# NCS_Wireless_Control_Card_Display_Connec.net
KiCad netlist of a schematic drawn in Altium Designer
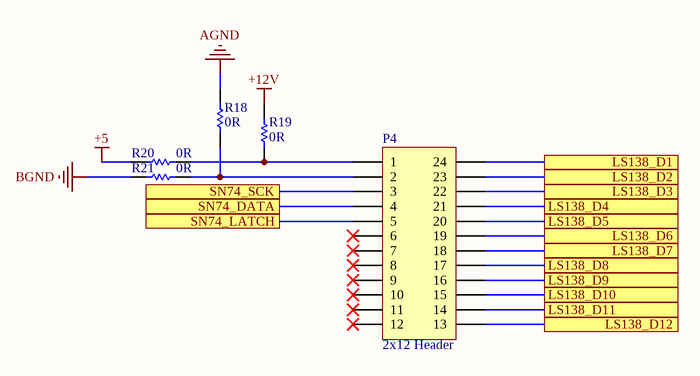
[diagram p0: NCS_Wireless_Control_Card_Display_Connector.SchDoc]

(export (version "E")
  (design (tool "Eeschema 10.0.6"))
  (components
    (comp (ref "P4")
      (value "2x12 Header")
      (footprint "2x12 header")
      (description "2.54mm Pitch C-Grid Header Low Profile Dual Row Vertical Shrouded 24 Circuits 0.38")
      (fields (field (name "MANUFACTURER") "Molex") (field (name "MANUFACTURER PART NUMBER") "0702462401"))
      (libsource (lib "schlib") (part "0702462401"))
    )
    (comp (ref "R18")
      (value "0R")
      (footprint "RC0805FR-7W330RL")
      (description "Res Thick Film 0805 330 Ohm 1% 0.25W(1/4W) ±200ppm/C Pad SMD T/R")
      (fields
        (field (name "MANUFACTURER") "Yageo")
        (field (name "MANUFACTURER PART NUMBER") "RC0805FR-7W330RL")
      )
      (libsource (lib "schlib") (part "RC0805FR-7W330RL"))
    )
    (comp (ref "R19")
      (value "0R")
      (footprint "RC0805FR-7W330RL")
      (description "Res Thick Film 0805 330 Ohm 1% 0.25W(1/4W) ±200ppm/C Pad SMD T/R")
      (fields
        (field (name "MANUFACTURER") "Yageo")
        (field (name "MANUFACTURER PART NUMBER") "RC0805FR-7W330RL")
      )
      (libsource (lib "schlib") (part "RC0805FR-7W330RL"))
    )
    (comp (ref "R20")
      (value "0R")
      (footprint "RC0805FR-7W330RL")
      (description "Res Thick Film 0805 330 Ohm 1% 0.25W(1/4W) ±200ppm/C Pad SMD T/R")
      (fields
        (field (name "MANUFACTURER") "Yageo")
        (field (name "MANUFACTURER PART NUMBER") "RC0805FR-7W330RL")
      )
      (libsource (lib "schlib") (part "RC0805FR-7W330RL"))
    )
    (comp (ref "R21")
      (value "0R")
      (footprint "RC0805FR-7W330RL")
      (description "Res Thick Film 0805 330 Ohm 1% 0.25W(1/4W) ±200ppm/C Pad SMD T/R")
      (fields
        (field (name "MANUFACTURER") "Yageo")
        (field (name "MANUFACTURER PART NUMBER") "RC0805FR-7W330RL")
      )
      (libsource (lib "schlib") (part "RC0805FR-7W330RL"))
    )
  )
  (nets
    (net (code "1") (name "+5") (class "Default")
      (node (ref "R20") (pin "2") (pinfunction "2_2") (pintype "passive"))
    )
    (net (code "2") (name "+12V") (class "Default")
      (node (ref "R19") (pin "2") (pinfunction "2_2") (pintype "passive"))
    )
    (net (code "3") (name "/LS138_D1") (class "Default")
      (node (ref "P4") (pin "24") (pinfunction "24_24") (pintype "passive"))
    )
    (net (code "4") (name "/LS138_D2") (class "Default")
      (node (ref "P4") (pin "23") (pinfunction "23_23") (pintype "passive"))
    )
    (net (code "5") (name "/LS138_D3") (class "Default")
      (node (ref "P4") (pin "22") (pinfunction "22_22") (pintype "passive"))
    )
    (net (code "6") (name "/LS138_D4") (class "Default")
      (node (ref "P4") (pin "21") (pinfunction "21_21") (pintype "passive"))
    )
    (net (code "7") (name "/LS138_D5") (class "Default")
      (node (ref "P4") (pin "20") (pinfunction "20_20") (pintype "passive"))
    )
    (net (code "8") (name "/LS138_D6") (class "Default")
      (node (ref "P4") (pin "19") (pinfunction "19_19") (pintype "passive"))
    )
    (net (code "9") (name "/LS138_D7") (class "Default")
      (node (ref "P4") (pin "18") (pinfunction "18_18") (pintype "passive"))
    )
    (net (code "10") (name "/LS138_D8") (class "Default")
      (node (ref "P4") (pin "17") (pinfunction "17_17") (pintype "passive"))
    )
    (net (code "11") (name "/LS138_D9") (class "Default")
      (node (ref "P4") (pin "16") (pinfunction "16_16") (pintype "passive"))
    )
    (net (code "12") (name "/LS138_D10") (class "Default")
      (node (ref "P4") (pin "15") (pinfunction "15_15") (pintype "passive"))
    )
    (net (code "13") (name "/LS138_D11") (class "Default")
      (node (ref "P4") (pin "14") (pinfunction "14_14") (pintype "passive"))
    )
    (net (code "14") (name "/LS138_D12") (class "Default")
      (node (ref "P4") (pin "13") (pinfunction "13_13") (pintype "passive"))
    )
    (net (code "15") (name "/SN74_DATA") (class "Default")
      (node (ref "P4") (pin "4") (pinfunction "4_4") (pintype "passive"))
    )
    (net (code "16") (name "/SN74_LATCH") (class "Default")
      (node (ref "P4") (pin "5") (pinfunction "5_5") (pintype "passive"))
    )
    (net (code "17") (name "/SN74_SCK") (class "Default")
      (node (ref "P4") (pin "3") (pinfunction "3_3") (pintype "passive"))
    )
    (net (code "18") (name "AGND") (class "Default")
      (node (ref "R18") (pin "2") (pinfunction "2_2") (pintype "passive"))
    )
    (net (code "19") (name "BGND") (class "Default")
      (node (ref "R21") (pin "2") (pinfunction "2_2") (pintype "passive"))
    )
    (net (code "20") (name "Net-(P4-Pad1)") (class "Default")
      (node (ref "P4") (pin "1") (pinfunction "1_1") (pintype "passive"))
      (node (ref "R19") (pin "1") (pinfunction "1_1") (pintype "passive"))
      (node (ref "R20") (pin "1") (pinfunction "1_1") (pintype "passive"))
    )
    (net (code "21") (name "Net-(P4-Pad2)") (class "Default")
      (node (ref "P4") (pin "2") (pinfunction "2_2") (pintype "passive"))
      (node (ref "R18") (pin "1") (pinfunction "1_1") (pintype "passive"))
      (node (ref "R21") (pin "1") (pinfunction "1_1") (pintype "passive"))
    )
    (net (code "22") (name "unconnected-(P4-Pad6)") (class "Default")
      (node (ref "P4") (pin "6") (pinfunction "6_6") (pintype "passive+no_connect"))
    )
    (net (code "23") (name "unconnected-(P4-Pad7)") (class "Default")
      (node (ref "P4") (pin "7") (pinfunction "7_7") (pintype "passive+no_connect"))
    )
    (net (code "24") (name "unconnected-(P4-Pad8)") (class "Default")
      (node (ref "P4") (pin "8") (pinfunction "8_8") (pintype "passive+no_connect"))
    )
    (net (code "25") (name "unconnected-(P4-Pad9)") (class "Default")
      (node (ref "P4") (pin "9") (pinfunction "9_9") (pintype "passive+no_connect"))
    )
    (net (code "26") (name "unconnected-(P4-Pad10)") (class "Default")
      (node (ref "P4") (pin "10") (pinfunction "10_10") (pintype "passive+no_connect"))
    )
    (net (code "27") (name "unconnected-(P4-Pad11)") (class "Default")
      (node (ref "P4") (pin "11") (pinfunction "11_11") (pintype "passive+no_connect"))
    )
    (net (code "28") (name "unconnected-(P4-Pad12)") (class "Default")
      (node (ref "P4") (pin "12") (pinfunction "12_12") (pintype "passive+no_connect"))
    )
  )
)
